# Power_Circuit.net
KiCad netlist of a schematic drawn in Altium Designer
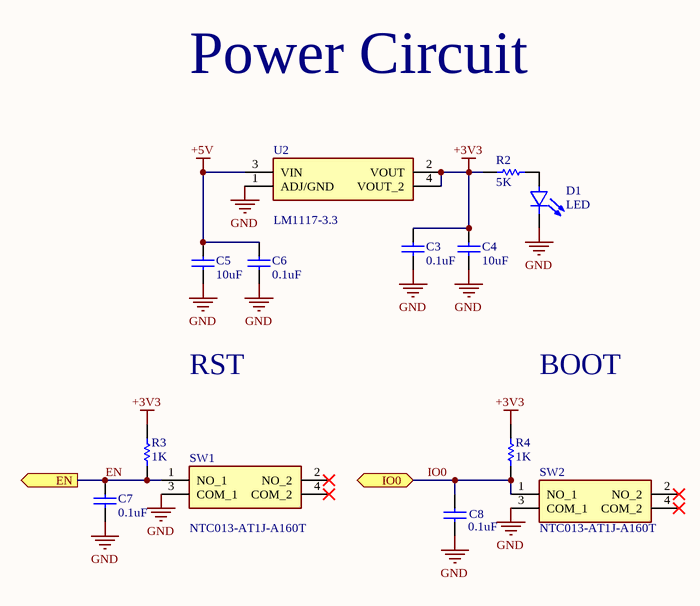
[diagram p0: Power Circuit.SchDoc]

(export (version "E")
  (design (tool "Eeschema 10.0.6"))
  (components
    (comp (ref "C3") (value "0.1uF") (footprint "C0402") (libsource (lib "Schlib1") (part "Cap")))
    (comp (ref "C4") (value "10uF") (footprint "C0402") (libsource (lib "Schlib1") (part "Cap")))
    (comp (ref "C5") (value "10uF") (footprint "C0402") (libsource (lib "Schlib1") (part "Cap")))
    (comp (ref "C6") (value "0.1uF") (footprint "C0402") (libsource (lib "Schlib1") (part "Cap")))
    (comp (ref "C7") (value "0.1uF") (footprint "C0402") (libsource (lib "Schlib1") (part "Cap")))
    (comp (ref "C8") (value "0.1uF") (footprint "C0402") (libsource (lib "Schlib1") (part "Cap")))
    (comp (ref "D1") (value "LED") (footprint "LED0402") (libsource (lib "Schlib1") (part "LED")))
    (comp (ref "R2") (value "5K") (footprint "R0402") (libsource (lib "Schlib1") (part "Res")))
    (comp (ref "R3") (value "1K") (footprint "R0402") (libsource (lib "Schlib1") (part "Res")))
    (comp (ref "R4") (value "1K") (footprint "R0402") (libsource (lib "Schlib1") (part "Res")))
    (comp (ref "SW1")
      (value "NTC013-AT1J-A160T")
      (footprint "Tactile sw")
      (libsource (lib "Schlib1") (part "NTC013-AT1J-A160T"))
    )
    (comp (ref "SW2")
      (value "NTC013-AT1J-A160T")
      (footprint "Tactile sw")
      (libsource (lib "Schlib1") (part "NTC013-AT1J-A160T"))
    )
    (comp (ref "U2")
      (value "LM1117-3.3")
      (footprint "SOT223")
      (description "Linear Voltage Regulator IC Positive Fixed 1 Output 800mA DDPAK/TO-263-3")
      (libsource (lib "Schlib1") (part "LM1117-3.3"))
    )
  )
  (nets
    (net (code "1") (name "+3V3") (class "Default")
      (node (ref "C3") (pin "02") (pinfunction "-_02") (pintype "passive"))
      (node (ref "C4") (pin "02") (pinfunction "-_02") (pintype "passive"))
      (node (ref "R2") (pin "02") (pinfunction "02_02") (pintype "passive"))
      (node (ref "R3") (pin "02") (pinfunction "02_02") (pintype "passive"))
      (node (ref "R4") (pin "02") (pinfunction "02_02") (pintype "passive"))
      (node (ref "U2") (pin "2") (pinfunction "VOUT_2") (pintype "power_in"))
      (node (ref "U2") (pin "4") (pinfunction "VOUT_2_4") (pintype "power_in"))
    )
    (net (code "2") (name "+5V") (class "Default")
      (node (ref "C5") (pin "02") (pinfunction "-_02") (pintype "passive"))
      (node (ref "C6") (pin "02") (pinfunction "-_02") (pintype "passive"))
      (node (ref "U2") (pin "3") (pinfunction "VIN_3") (pintype "power_in"))
    )
    (net (code "3") (name "/EN") (class "Default")
      (node (ref "C7") (pin "02") (pinfunction "-_02") (pintype "passive"))
      (node (ref "R3") (pin "01") (pinfunction "01_01") (pintype "passive"))
      (node (ref "SW1") (pin "1") (pinfunction "NO_1_1") (pintype "passive"))
    )
    (net (code "4") (name "/IO0") (class "Default")
      (node (ref "C8") (pin "02") (pinfunction "-_02") (pintype "passive"))
      (node (ref "R4") (pin "01") (pinfunction "01_01") (pintype "passive"))
      (node (ref "SW2") (pin "1") (pinfunction "NO_1_1") (pintype "passive"))
    )
    (net (code "5") (name "GND") (class "Default")
      (node (ref "C3") (pin "01") (pinfunction "+_01") (pintype "passive"))
      (node (ref "C4") (pin "01") (pinfunction "+_01") (pintype "passive"))
      (node (ref "C5") (pin "01") (pinfunction "+_01") (pintype "passive"))
      (node (ref "C6") (pin "01") (pinfunction "+_01") (pintype "passive"))
      (node (ref "C7") (pin "01") (pinfunction "+_01") (pintype "passive"))
      (node (ref "C8") (pin "01") (pinfunction "+_01") (pintype "passive"))
      (node (ref "D1") (pin "1") (pinfunction "C_1") (pintype "passive"))
      (node (ref "SW1") (pin "3") (pinfunction "COM_1_3") (pintype "passive"))
      (node (ref "SW2") (pin "3") (pinfunction "COM_1_3") (pintype "passive"))
      (node (ref "U2") (pin "1") (pinfunction "ADJ/GND_1") (pintype "passive"))
    )
    (net (code "6") (name "Net-(D1-A)") (class "Default")
      (node (ref "D1") (pin "2") (pinfunction "A_2") (pintype "passive"))
      (node (ref "R2") (pin "01") (pinfunction "01_01") (pintype "passive"))
    )
    (net (code "7") (name "unconnected-(SW1-COM_2-Pad4)") (class "Default")
      (node (ref "SW1") (pin "4") (pinfunction "COM_2_4") (pintype "passive+no_connect"))
    )
    (net (code "8") (name "unconnected-(SW1-NO_2-Pad2)") (class "Default")
      (node (ref "SW1") (pin "2") (pinfunction "NO_2_2") (pintype "passive+no_connect"))
    )
    (net (code "9") (name "unconnected-(SW2-COM_2-Pad4)") (class "Default")
      (node (ref "SW2") (pin "4") (pinfunction "COM_2_4") (pintype "passive+no_connect"))
    )
    (net (code "10") (name "unconnected-(SW2-NO_2-Pad2)") (class "Default")
      (node (ref "SW2") (pin "2") (pinfunction "NO_2_2") (pintype "passive+no_connect"))
    )
  )
)
